# Reverse_Polarity_Protection.net
KiCad netlist of a schematic drawn in Altium Designer
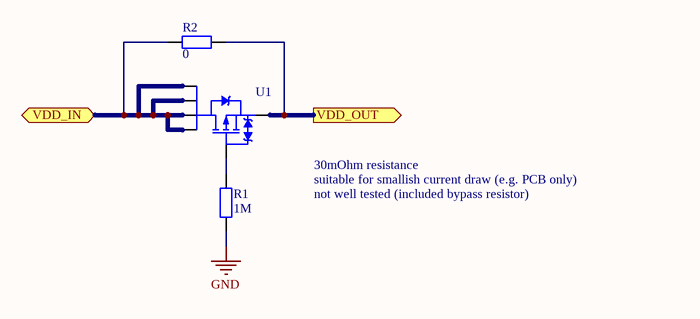
[diagram p0: Reverse Polarity Protection.SchDoc]

(export (version "E")
  (design (tool "Eeschema 10.0.6"))
  (components
    (comp (ref "R1")
      (value "1M")
      (footprint "R0603")
      (description "Resistor")
      (fields (field (name "Comment") "Res"))
      (libsource (lib "") (part "Res2_1"))
    )
    (comp (ref "R2")
      (value "0")
      (footprint "R0603")
      (description "Resistor")
      (fields (field (name "Comment") "Res"))
      (libsource (lib "Miscellaneous Devices") (part "Res2"))
    )
    (comp (ref "U1")
      (value "MOSFET P FDC608PZ")
      (footprint "FDC608PZ")
      (description "FAIRCHILD SEMICONDUCTOR - FDC608PZ - MOSFET, P, SMD, SSOT-6")
      (libsource (lib "Mosfet P FDC608PZ") (part "MOSFET P FDC608PZ"))
    )
  )
  (nets
    (net (code "1") (name "/VDD_IN") (class "Default")
      (node (ref "R2") (pin "1") (pinfunction "1_1") (pintype "passive"))
      (node (ref "U1") (pin "1") (pinfunction "D_1") (pintype "passive"))
      (node (ref "U1") (pin "2") (pinfunction "D_2") (pintype "passive"))
      (node (ref "U1") (pin "5") (pinfunction "D_5") (pintype "passive"))
      (node (ref "U1") (pin "6") (pinfunction "D_6") (pintype "passive"))
    )
    (net (code "2") (name "/VDD_OUT") (class "Default")
      (node (ref "R2") (pin "2") (pinfunction "2_2") (pintype "passive"))
      (node (ref "U1") (pin "4") (pinfunction "S_4") (pintype "passive"))
    )
    (net (code "3") (name "GND") (class "Default")
      (node (ref "R1") (pin "1") (pinfunction "1_1") (pintype "passive"))
    )
    (net (code "4") (name "Net-(U1-G)") (class "Default")
      (node (ref "R1") (pin "2") (pinfunction "2_2") (pintype "passive"))
      (node (ref "U1") (pin "3") (pinfunction "G_3") (pintype "passive"))
    )
  )
)
